# DIOT_signal_routing.net
KiCad netlist of a schematic drawn in Altium Designer
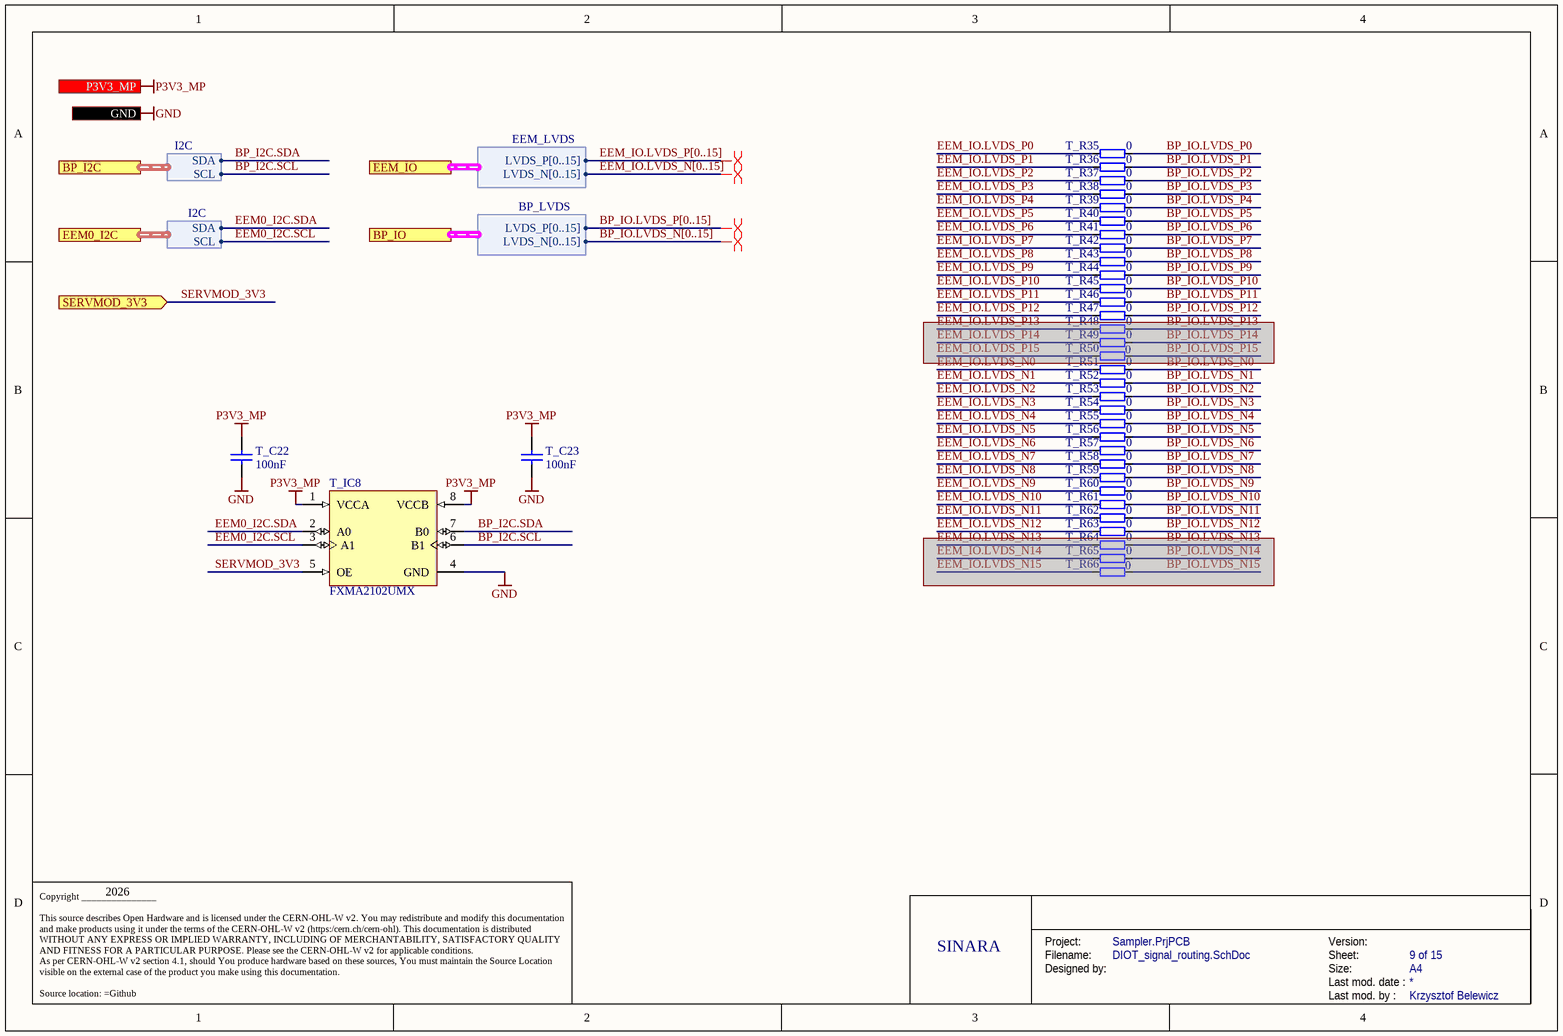
[diagram p0: DIOT_signal_routing.SchDoc]

(export (version "E")
  (design (tool "Eeschema 10.0.6"))
  (components
    (comp (ref "T_C22")
      (value "100nF")
      (footprint "CAPC1005X55N")
      (description "Non-polarised capacitor")
      (fields
        (field (name "PART NUMBER") "CC0402_100NF_50V_10%_X7R")
        (field (name "VOLTAGE") "50V")
        (field (name "AUTHOR") "CERN DEM MR")
      )
      (libsource (lib "Capacitors") (part "Capacitor - non polarized"))
    )
    (comp (ref "T_C23")
      (value "100nF")
      (footprint "CAPC1005X55N")
      (description "Non-polarised capacitor")
      (fields
        (field (name "PART NUMBER") "CC0402_100NF_50V_10%_X7R")
        (field (name "VOLTAGE") "50V")
        (field (name "AUTHOR") "CERN DEM MR")
      )
      (libsource (lib "Capacitors") (part "Capacitor - non polarized"))
    )
    (comp (ref "T_IC8")
      (value "FXMA2102UMX")
      (footprint "FXMA2102UMX")
      (description "Dual Supply 2-Bit Voltage Translator/Buffer/Repeater Isolator for I2C Applications")
      (fields (field (name "MANUFACTURER") "Onsemi"))
      (libsource (lib "TechnoSystem Workspace") (part "FXMA2102UMX"))
    )
    (comp (ref "T_R35")
      (value "0")
      (footprint "RESC1005X40N")
      (description "Resistor")
      (fields
        (field (name "PART NUMBER") "R0402_0R_JUMPER")
        (field (name "MANUFACTURER") "GENERIC")
        (field (name "AUTHOR") "CERN DEM JLC")
      )
      (libsource (lib "Resistors") (part "Resistor"))
    )
    (comp (ref "T_R36")
      (value "0")
      (footprint "RESC1005X40N")
      (description "Resistor")
      (fields
        (field (name "PART NUMBER") "R0402_0R_JUMPER")
        (field (name "MANUFACTURER") "GENERIC")
        (field (name "AUTHOR") "CERN DEM JLC")
      )
      (libsource (lib "Resistors") (part "Resistor"))
    )
    (comp (ref "T_R37")
      (value "0")
      (footprint "RESC1005X40N")
      (description "Resistor")
      (fields
        (field (name "PART NUMBER") "R0402_0R_JUMPER")
        (field (name "MANUFACTURER") "GENERIC")
        (field (name "AUTHOR") "CERN DEM JLC")
      )
      (libsource (lib "Resistors") (part "Resistor"))
    )
    (comp (ref "T_R38")
      (value "0")
      (footprint "RESC1005X40N")
      (description "Resistor")
      (fields
        (field (name "PART NUMBER") "R0402_0R_JUMPER")
        (field (name "MANUFACTURER") "GENERIC")
        (field (name "AUTHOR") "CERN DEM JLC")
      )
      (libsource (lib "Resistors") (part "Resistor"))
    )
    (comp (ref "T_R39")
      (value "0")
      (footprint "RESC1005X40N")
      (description "Resistor")
      (fields
        (field (name "PART NUMBER") "R0402_0R_JUMPER")
        (field (name "MANUFACTURER") "GENERIC")
        (field (name "AUTHOR") "CERN DEM JLC")
      )
      (libsource (lib "Resistors") (part "Resistor"))
    )
    (comp (ref "T_R40")
      (value "0")
      (footprint "RESC1005X40N")
      (description "Resistor")
      (fields
        (field (name "PART NUMBER") "R0402_0R_JUMPER")
        (field (name "MANUFACTURER") "GENERIC")
        (field (name "AUTHOR") "CERN DEM JLC")
      )
      (libsource (lib "Resistors") (part "Resistor"))
    )
    (comp (ref "T_R41")
      (value "0")
      (footprint "RESC1005X40N")
      (description "Resistor")
      (fields
        (field (name "PART NUMBER") "R0402_0R_JUMPER")
        (field (name "MANUFACTURER") "GENERIC")
        (field (name "AUTHOR") "CERN DEM JLC")
      )
      (libsource (lib "Resistors") (part "Resistor"))
    )
    (comp (ref "T_R42")
      (value "0")
      (footprint "RESC1005X40N")
      (description "Resistor")
      (fields
        (field (name "PART NUMBER") "R0402_0R_JUMPER")
        (field (name "MANUFACTURER") "GENERIC")
        (field (name "AUTHOR") "CERN DEM JLC")
      )
      (libsource (lib "Resistors") (part "Resistor"))
    )
    (comp (ref "T_R43")
      (value "0")
      (footprint "RESC1005X40N")
      (description "Resistor")
      (fields
        (field (name "PART NUMBER") "R0402_0R_JUMPER")
        (field (name "MANUFACTURER") "GENERIC")
        (field (name "AUTHOR") "CERN DEM JLC")
      )
      (libsource (lib "Resistors") (part "Resistor"))
    )
    (comp (ref "T_R44")
      (value "0")
      (footprint "RESC1005X40N")
      (description "Resistor")
      (fields
        (field (name "PART NUMBER") "R0402_0R_JUMPER")
        (field (name "MANUFACTURER") "GENERIC")
        (field (name "AUTHOR") "CERN DEM JLC")
      )
      (libsource (lib "Resistors") (part "Resistor"))
    )
    (comp (ref "T_R45")
      (value "0")
      (footprint "RESC1005X40N")
      (description "Resistor")
      (fields
        (field (name "PART NUMBER") "R0402_0R_JUMPER")
        (field (name "MANUFACTURER") "GENERIC")
        (field (name "AUTHOR") "CERN DEM JLC")
      )
      (libsource (lib "Resistors") (part "Resistor"))
    )
    (comp (ref "T_R46")
      (value "0")
      (footprint "RESC1005X40N")
      (description "Resistor")
      (fields
        (field (name "PART NUMBER") "R0402_0R_JUMPER")
        (field (name "MANUFACTURER") "GENERIC")
        (field (name "AUTHOR") "CERN DEM JLC")
      )
      (libsource (lib "Resistors") (part "Resistor"))
    )
    (comp (ref "T_R47")
      (value "0")
      (footprint "RESC1005X40N")
      (description "Resistor")
      (fields
        (field (name "PART NUMBER") "R0402_0R_JUMPER")
        (field (name "MANUFACTURER") "GENERIC")
        (field (name "AUTHOR") "CERN DEM JLC")
      )
      (libsource (lib "Resistors") (part "Resistor"))
    )
    (comp (ref "T_R48")
      (value "0")
      (footprint "RESC1005X40N")
      (description "Resistor")
      (fields
        (field (name "PART NUMBER") "R0402_0R_JUMPER")
        (field (name "MANUFACTURER") "GENERIC")
        (field (name "AUTHOR") "CERN DEM JLC")
      )
      (libsource (lib "Resistors") (part "Resistor"))
    )
    (comp (ref "T_R49")
      (value "0")
      (footprint "RESC1005X40N")
      (description "Resistor")
      (fields
        (field (name "PART NUMBER") "R0402_0R_JUMPER")
        (field (name "MANUFACTURER") "GENERIC")
        (field (name "AUTHOR") "CERN DEM JLC")
      )
      (libsource (lib "Resistors") (part "Resistor"))
    )
    (comp (ref "T_R50")
      (value "0")
      (footprint "RESC1005X40N")
      (description "Resistor")
      (fields
        (field (name "PART NUMBER") "R0402_0R_JUMPER")
        (field (name "MANUFACTURER") "GENERIC")
        (field (name "AUTHOR") "CERN DEM JLC")
      )
      (libsource (lib "Resistors") (part "Resistor"))
    )
    (comp (ref "T_R51")
      (value "0")
      (footprint "RESC1005X40N")
      (description "Resistor")
      (fields
        (field (name "PART NUMBER") "R0402_0R_JUMPER")
        (field (name "MANUFACTURER") "GENERIC")
        (field (name "AUTHOR") "CERN DEM JLC")
      )
      (libsource (lib "Resistors") (part "Resistor"))
    )
    (comp (ref "T_R52")
      (value "0")
      (footprint "RESC1005X40N")
      (description "Resistor")
      (fields
        (field (name "PART NUMBER") "R0402_0R_JUMPER")
        (field (name "MANUFACTURER") "GENERIC")
        (field (name "AUTHOR") "CERN DEM JLC")
      )
      (libsource (lib "Resistors") (part "Resistor"))
    )
    (comp (ref "T_R53")
      (value "0")
      (footprint "RESC1005X40N")
      (description "Resistor")
      (fields
        (field (name "PART NUMBER") "R0402_0R_JUMPER")
        (field (name "MANUFACTURER") "GENERIC")
        (field (name "AUTHOR") "CERN DEM JLC")
      )
      (libsource (lib "Resistors") (part "Resistor"))
    )
    (comp (ref "T_R54")
      (value "0")
      (footprint "RESC1005X40N")
      (description "Resistor")
      (fields
        (field (name "PART NUMBER") "R0402_0R_JUMPER")
        (field (name "MANUFACTURER") "GENERIC")
        (field (name "AUTHOR") "CERN DEM JLC")
      )
      (libsource (lib "Resistors") (part "Resistor"))
    )
    (comp (ref "T_R55")
      (value "0")
      (footprint "RESC1005X40N")
      (description "Resistor")
      (fields
        (field (name "PART NUMBER") "R0402_0R_JUMPER")
        (field (name "MANUFACTURER") "GENERIC")
        (field (name "AUTHOR") "CERN DEM JLC")
      )
      (libsource (lib "Resistors") (part "Resistor"))
    )
    (comp (ref "T_R56")
      (value "0")
      (footprint "RESC1005X40N")
      (description "Resistor")
      (fields
        (field (name "PART NUMBER") "R0402_0R_JUMPER")
        (field (name "MANUFACTURER") "GENERIC")
        (field (name "AUTHOR") "CERN DEM JLC")
      )
      (libsource (lib "Resistors") (part "Resistor"))
    )
    (comp (ref "T_R57")
      (value "0")
      (footprint "RESC1005X40N")
      (description "Resistor")
      (fields
        (field (name "PART NUMBER") "R0402_0R_JUMPER")
        (field (name "MANUFACTURER") "GENERIC")
        (field (name "AUTHOR") "CERN DEM JLC")
      )
      (libsource (lib "Resistors") (part "Resistor"))
    )
    (comp (ref "T_R58")
      (value "0")
      (footprint "RESC1005X40N")
      (description "Resistor")
      (fields
        (field (name "PART NUMBER") "R0402_0R_JUMPER")
        (field (name "MANUFACTURER") "GENERIC")
        (field (name "AUTHOR") "CERN DEM JLC")
      )
      (libsource (lib "Resistors") (part "Resistor"))
    )
    (comp (ref "T_R59")
      (value "0")
      (footprint "RESC1005X40N")
      (description "Resistor")
      (fields
        (field (name "PART NUMBER") "R0402_0R_JUMPER")
        (field (name "MANUFACTURER") "GENERIC")
        (field (name "AUTHOR") "CERN DEM JLC")
      )
      (libsource (lib "Resistors") (part "Resistor"))
    )
    (comp (ref "T_R60")
      (value "0")
      (footprint "RESC1005X40N")
      (description "Resistor")
      (fields
        (field (name "PART NUMBER") "R0402_0R_JUMPER")
        (field (name "MANUFACTURER") "GENERIC")
        (field (name "AUTHOR") "CERN DEM JLC")
      )
      (libsource (lib "Resistors") (part "Resistor"))
    )
    (comp (ref "T_R61")
      (value "0")
      (footprint "RESC1005X40N")
      (description "Resistor")
      (fields
        (field (name "PART NUMBER") "R0402_0R_JUMPER")
        (field (name "MANUFACTURER") "GENERIC")
        (field (name "AUTHOR") "CERN DEM JLC")
      )
      (libsource (lib "Resistors") (part "Resistor"))
    )
    (comp (ref "T_R62")
      (value "0")
      (footprint "RESC1005X40N")
      (description "Resistor")
      (fields
        (field (name "PART NUMBER") "R0402_0R_JUMPER")
        (field (name "MANUFACTURER") "GENERIC")
        (field (name "AUTHOR") "CERN DEM JLC")
      )
      (libsource (lib "Resistors") (part "Resistor"))
    )
    (comp (ref "T_R63")
      (value "0")
      (footprint "RESC1005X40N")
      (description "Resistor")
      (fields
        (field (name "PART NUMBER") "R0402_0R_JUMPER")
        (field (name "MANUFACTURER") "GENERIC")
        (field (name "AUTHOR") "CERN DEM JLC")
      )
      (libsource (lib "Resistors") (part "Resistor"))
    )
    (comp (ref "T_R64")
      (value "0")
      (footprint "RESC1005X40N")
      (description "Resistor")
      (fields
        (field (name "PART NUMBER") "R0402_0R_JUMPER")
        (field (name "MANUFACTURER") "GENERIC")
        (field (name "AUTHOR") "CERN DEM JLC")
      )
      (libsource (lib "Resistors") (part "Resistor"))
    )
    (comp (ref "T_R65")
      (value "0")
      (footprint "RESC1005X40N")
      (description "Resistor")
      (fields
        (field (name "PART NUMBER") "R0402_0R_JUMPER")
        (field (name "MANUFACTURER") "GENERIC")
        (field (name "AUTHOR") "CERN DEM JLC")
      )
      (libsource (lib "Resistors") (part "Resistor"))
    )
    (comp (ref "T_R66")
      (value "0")
      (footprint "RESC1005X40N")
      (description "Resistor")
      (fields
        (field (name "PART NUMBER") "R0402_0R_JUMPER")
        (field (name "MANUFACTURER") "GENERIC")
        (field (name "AUTHOR") "CERN DEM JLC")
      )
      (libsource (lib "Resistors") (part "Resistor"))
    )
  )
  (nets
    (net (code "4") (name "/BP_I2C.SCL") (class "Default")
      (node (ref "T_IC8") (pin "6") (pinfunction "B1_6") (pintype "bidirectional"))
    )
    (net (code "5") (name "/BP_I2C.SDA") (class "Default")
      (node (ref "T_IC8") (pin "7") (pinfunction "B0_7") (pintype "bidirectional"))
    )
    (net (code "6") (name "/BP_IO.LVDS_N0") (class "Default")
      (node (ref "T_R51") (pin "1") (pinfunction "1_1") (pintype "passive"))
    )
    (net (code "7") (name "/BP_IO.LVDS_N1") (class "Default")
      (node (ref "T_R52") (pin "1") (pinfunction "1_1") (pintype "passive"))
    )
    (net (code "8") (name "/BP_IO.LVDS_N2") (class "Default")
      (node (ref "T_R53") (pin "1") (pinfunction "1_1") (pintype "passive"))
    )
    (net (code "9") (name "/BP_IO.LVDS_N3") (class "Default")
      (node (ref "T_R54") (pin "1") (pinfunction "1_1") (pintype "passive"))
    )
    (net (code "10") (name "/BP_IO.LVDS_N4") (class "Default")
      (node (ref "T_R55") (pin "1") (pinfunction "1_1") (pintype "passive"))
    )
    (net (code "11") (name "/BP_IO.LVDS_N5") (class "Default")
      (node (ref "T_R56") (pin "1") (pinfunction "1_1") (pintype "passive"))
    )
    (net (code "12") (name "/BP_IO.LVDS_N6") (class "Default")
      (node (ref "T_R57") (pin "1") (pinfunction "1_1") (pintype "passive"))
    )
    (net (code "13") (name "/BP_IO.LVDS_N7") (class "Default")
      (node (ref "T_R58") (pin "1") (pinfunction "1_1") (pintype "passive"))
    )
    (net (code "14") (name "/BP_IO.LVDS_N8") (class "Default")
      (node (ref "T_R59") (pin "1") (pinfunction "1_1") (pintype "passive"))
    )
    (net (code "15") (name "/BP_IO.LVDS_N9") (class "Default")
      (node (ref "T_R60") (pin "1") (pinfunction "1_1") (pintype "passive"))
    )
    (net (code "16") (name "/BP_IO.LVDS_N10") (class "Default")
      (node (ref "T_R61") (pin "1") (pinfunction "1_1") (pintype "passive"))
    )
    (net (code "17") (name "/BP_IO.LVDS_N11") (class "Default")
      (node (ref "T_R62") (pin "1") (pinfunction "1_1") (pintype "passive"))
    )
    (net (code "18") (name "/BP_IO.LVDS_N12") (class "Default")
      (node (ref "T_R63") (pin "1") (pinfunction "1_1") (pintype "passive"))
    )
    (net (code "19") (name "/BP_IO.LVDS_N13") (class "Default")
      (node (ref "T_R64") (pin "1") (pinfunction "1_1") (pintype "passive"))
    )
    (net (code "20") (name "/BP_IO.LVDS_N14") (class "Default")
      (node (ref "T_R65") (pin "1") (pinfunction "1_1") (pintype "passive"))
    )
    (net (code "21") (name "/BP_IO.LVDS_N15") (class "Default")
      (node (ref "T_R66") (pin "2") (pinfunction "2_2") (pintype "passive"))
    )
    (net (code "22") (name "/BP_IO.LVDS_P0") (class "Default")
      (node (ref "T_R35") (pin "1") (pinfunction "1_1") (pintype "passive"))
    )
    (net (code "23") (name "/BP_IO.LVDS_P1") (class "Default")
      (node (ref "T_R36") (pin "1") (pinfunction "1_1") (pintype "passive"))
    )
    (net (code "24") (name "/BP_IO.LVDS_P2") (class "Default")
      (node (ref "T_R37") (pin "1") (pinfunction "1_1") (pintype "passive"))
    )
    (net (code "25") (name "/BP_IO.LVDS_P3") (class "Default")
      (node (ref "T_R38") (pin "1") (pinfunction "1_1") (pintype "passive"))
    )
    (net (code "26") (name "/BP_IO.LVDS_P4") (class "Default")
      (node (ref "T_R39") (pin "1") (pinfunction "1_1") (pintype "passive"))
    )
    (net (code "27") (name "/BP_IO.LVDS_P5") (class "Default")
      (node (ref "T_R40") (pin "1") (pinfunction "1_1") (pintype "passive"))
    )
    (net (code "28") (name "/BP_IO.LVDS_P6") (class "Default")
      (node (ref "T_R41") (pin "1") (pinfunction "1_1") (pintype "passive"))
    )
    (net (code "29") (name "/BP_IO.LVDS_P7") (class "Default")
      (node (ref "T_R42") (pin "1") (pinfunction "1_1") (pintype "passive"))
    )
    (net (code "30") (name "/BP_IO.LVDS_P8") (class "Default")
      (node (ref "T_R43") (pin "1") (pinfunction "1_1") (pintype "passive"))
    )
    (net (code "31") (name "/BP_IO.LVDS_P9") (class "Default")
      (node (ref "T_R44") (pin "1") (pinfunction "1_1") (pintype "passive"))
    )
    (net (code "32") (name "/BP_IO.LVDS_P10") (class "Default")
      (node (ref "T_R45") (pin "1") (pinfunction "1_1") (pintype "passive"))
    )
    (net (code "33") (name "/BP_IO.LVDS_P11") (class "Default")
      (node (ref "T_R46") (pin "1") (pinfunction "1_1") (pintype "passive"))
    )
    (net (code "34") (name "/BP_IO.LVDS_P12") (class "Default")
      (node (ref "T_R47") (pin "1") (pinfunction "1_1") (pintype "passive"))
    )
    (net (code "35") (name "/BP_IO.LVDS_P13") (class "Default")
      (node (ref "T_R48") (pin "1") (pinfunction "1_1") (pintype "passive"))
    )
    (net (code "36") (name "/BP_IO.LVDS_P14") (class "Default")
      (node (ref "T_R49") (pin "1") (pinfunction "1_1") (pintype "passive"))
    )
    (net (code "37") (name "/BP_IO.LVDS_P15") (class "Default")
      (node (ref "T_R50") (pin "2") (pinfunction "2_2") (pintype "passive"))
    )
    (net (code "40") (name "/EEM0_I2C.SCL") (class "Default")
      (node (ref "T_IC8") (pin "3") (pinfunction "A1_3") (pintype "bidirectional"))
    )
    (net (code "41") (name "/EEM0_I2C.SDA") (class "Default")
      (node (ref "T_IC8") (pin "2") (pinfunction "A0_2") (pintype "bidirectional"))
    )
    (net (code "42") (name "/EEM_IO.LVDS_N0") (class "Default")
      (node (ref "T_R51") (pin "2") (pinfunction "2_2") (pintype "passive"))
    )
    (net (code "43") (name "/EEM_IO.LVDS_N1") (class "Default")
      (node (ref "T_R52") (pin "2") (pinfunction "2_2") (pintype "passive"))
    )
    (net (code "44") (name "/EEM_IO.LVDS_N2") (class "Default")
      (node (ref "T_R53") (pin "2") (pinfunction "2_2") (pintype "passive"))
    )
    (net (code "45") (name "/EEM_IO.LVDS_N3") (class "Default")
      (node (ref "T_R54") (pin "2") (pinfunction "2_2") (pintype "passive"))
    )
    (net (code "46") (name "/EEM_IO.LVDS_N4") (class "Default")
      (node (ref "T_R55") (pin "2") (pinfunction "2_2") (pintype "passive"))
    )
    (net (code "47") (name "/EEM_IO.LVDS_N5") (class "Default")
      (node (ref "T_R56") (pin "2") (pinfunction "2_2") (pintype "passive"))
    )
    (net (code "48") (name "/EEM_IO.LVDS_N6") (class "Default")
      (node (ref "T_R57") (pin "2") (pinfunction "2_2") (pintype "passive"))
    )
    (net (code "49") (name "/EEM_IO.LVDS_N7") (class "Default")
      (node (ref "T_R58") (pin "2") (pinfunction "2_2") (pintype "passive"))
    )
    (net (code "50") (name "/EEM_IO.LVDS_N8") (class "Default")
      (node (ref "T_R59") (pin "2") (pinfunction "2_2") (pintype "passive"))
    )
    (net (code "51") (name "/EEM_IO.LVDS_N9") (class "Default")
      (node (ref "T_R60") (pin "2") (pinfunction "2_2") (pintype "passive"))
    )
    (net (code "52") (name "/EEM_IO.LVDS_N10") (class "Default")
      (node (ref "T_R61") (pin "2") (pinfunction "2_2") (pintype "passive"))
    )
    (net (code "53") (name "/EEM_IO.LVDS_N11") (class "Default")
      (node (ref "T_R62") (pin "2") (pinfunction "2_2") (pintype "passive"))
    )
    (net (code "54") (name "/EEM_IO.LVDS_N12") (class "Default")
      (node (ref "T_R63") (pin "2") (pinfunction "2_2") (pintype "passive"))
    )
    (net (code "55") (name "/EEM_IO.LVDS_N13") (class "Default")
      (node (ref "T_R64") (pin "2") (pinfunction "2_2") (pintype "passive"))
    )
    (net (code "56") (name "/EEM_IO.LVDS_N14") (class "Default")
      (node (ref "T_R65") (pin "2") (pinfunction "2_2") (pintype "passive"))
    )
    (net (code "57") (name "/EEM_IO.LVDS_N15") (class "Default")
      (node (ref "T_R66") (pin "1") (pinfunction "1_1") (pintype "passive"))
    )
    (net (code "59") (name "/EEM_IO.LVDS_P0") (class "Default")
      (node (ref "T_R35") (pin "2") (pinfunction "2_2") (pintype "passive"))
    )
    (net (code "60") (name "/EEM_IO.LVDS_P1") (class "Default")
      (node (ref "T_R36") (pin "2") (pinfunction "2_2") (pintype "passive"))
    )
    (net (code "61") (name "/EEM_IO.LVDS_P2") (class "Default")
      (node (ref "T_R37") (pin "2") (pinfunction "2_2") (pintype "passive"))
    )
    (net (code "62") (name "/EEM_IO.LVDS_P3") (class "Default")
      (node (ref "T_R38") (pin "2") (pinfunction "2_2") (pintype "passive"))
    )
    (net (code "63") (name "/EEM_IO.LVDS_P4") (class "Default")
      (node (ref "T_R39") (pin "2") (pinfunction "2_2") (pintype "passive"))
    )
    (net (code "64") (name "/EEM_IO.LVDS_P5") (class "Default")
      (node (ref "T_R40") (pin "2") (pinfunction "2_2") (pintype "passive"))
    )
    (net (code "65") (name "/EEM_IO.LVDS_P6") (class "Default")
      (node (ref "T_R41") (pin "2") (pinfunction "2_2") (pintype "passive"))
    )
    (net (code "66") (name "/EEM_IO.LVDS_P7") (class "Default")
      (node (ref "T_R42") (pin "2") (pinfunction "2_2") (pintype "passive"))
    )
    (net (code "67") (name "/EEM_IO.LVDS_P8") (class "Default")
      (node (ref "T_R43") (pin "2") (pinfunction "2_2") (pintype "passive"))
    )
    (net (code "68") (name "/EEM_IO.LVDS_P9") (class "Default")
      (node (ref "T_R44") (pin "2") (pinfunction "2_2") (pintype "passive"))
    )
    (net (code "69") (name "/EEM_IO.LVDS_P10") (class "Default")
      (node (ref "T_R45") (pin "2") (pinfunction "2_2") (pintype "passive"))
    )
    (net (code "70") (name "/EEM_IO.LVDS_P11") (class "Default")
      (node (ref "T_R46") (pin "2") (pinfunction "2_2") (pintype "passive"))
    )
    (net (code "71") (name "/EEM_IO.LVDS_P12") (class "Default")
      (node (ref "T_R47") (pin "2") (pinfunction "2_2") (pintype "passive"))
    )
    (net (code "72") (name "/EEM_IO.LVDS_P13") (class "Default")
      (node (ref "T_R48") (pin "2") (pinfunction "2_2") (pintype "passive"))
    )
    (net (code "73") (name "/EEM_IO.LVDS_P14") (class "Default")
      (node (ref "T_R49") (pin "2") (pinfunction "2_2") (pintype "passive"))
    )
    (net (code "74") (name "/EEM_IO.LVDS_P15") (class "Default")
      (node (ref "T_R50") (pin "1") (pinfunction "1_1") (pintype "passive"))
    )
    (net (code "76") (name "/SERVMOD_3V3") (class "Default")
      (node (ref "T_IC8") (pin "5") (pinfunction "OE_5") (pintype "input"))
    )
    (net (code "79") (name "GND") (class "Default")
      (node (ref "T_C22") (pin "1") (pinfunction "1_1") (pintype "passive"))
      (node (ref "T_C23") (pin "1") (pinfunction "1_1") (pintype "passive"))
      (node (ref "T_IC8") (pin "4") (pinfunction "GND_4") (pintype "power_in"))
    )
    (net (code "80") (name "P3V3_MP") (class "Default")
      (node (ref "T_C22") (pin "2") (pinfunction "2_2") (pintype "passive"))
      (node (ref "T_C23") (pin "2") (pinfunction "2_2") (pintype "passive"))
      (node (ref "T_IC8") (pin "1") (pinfunction "VCCA_1") (pintype "input"))
      (node (ref "T_IC8") (pin "8") (pinfunction "VCCB_8") (pintype "input"))
    )
  )
)
